# Channel_w_Stim.net
KiCad netlist of a schematic drawn in Altium Designer
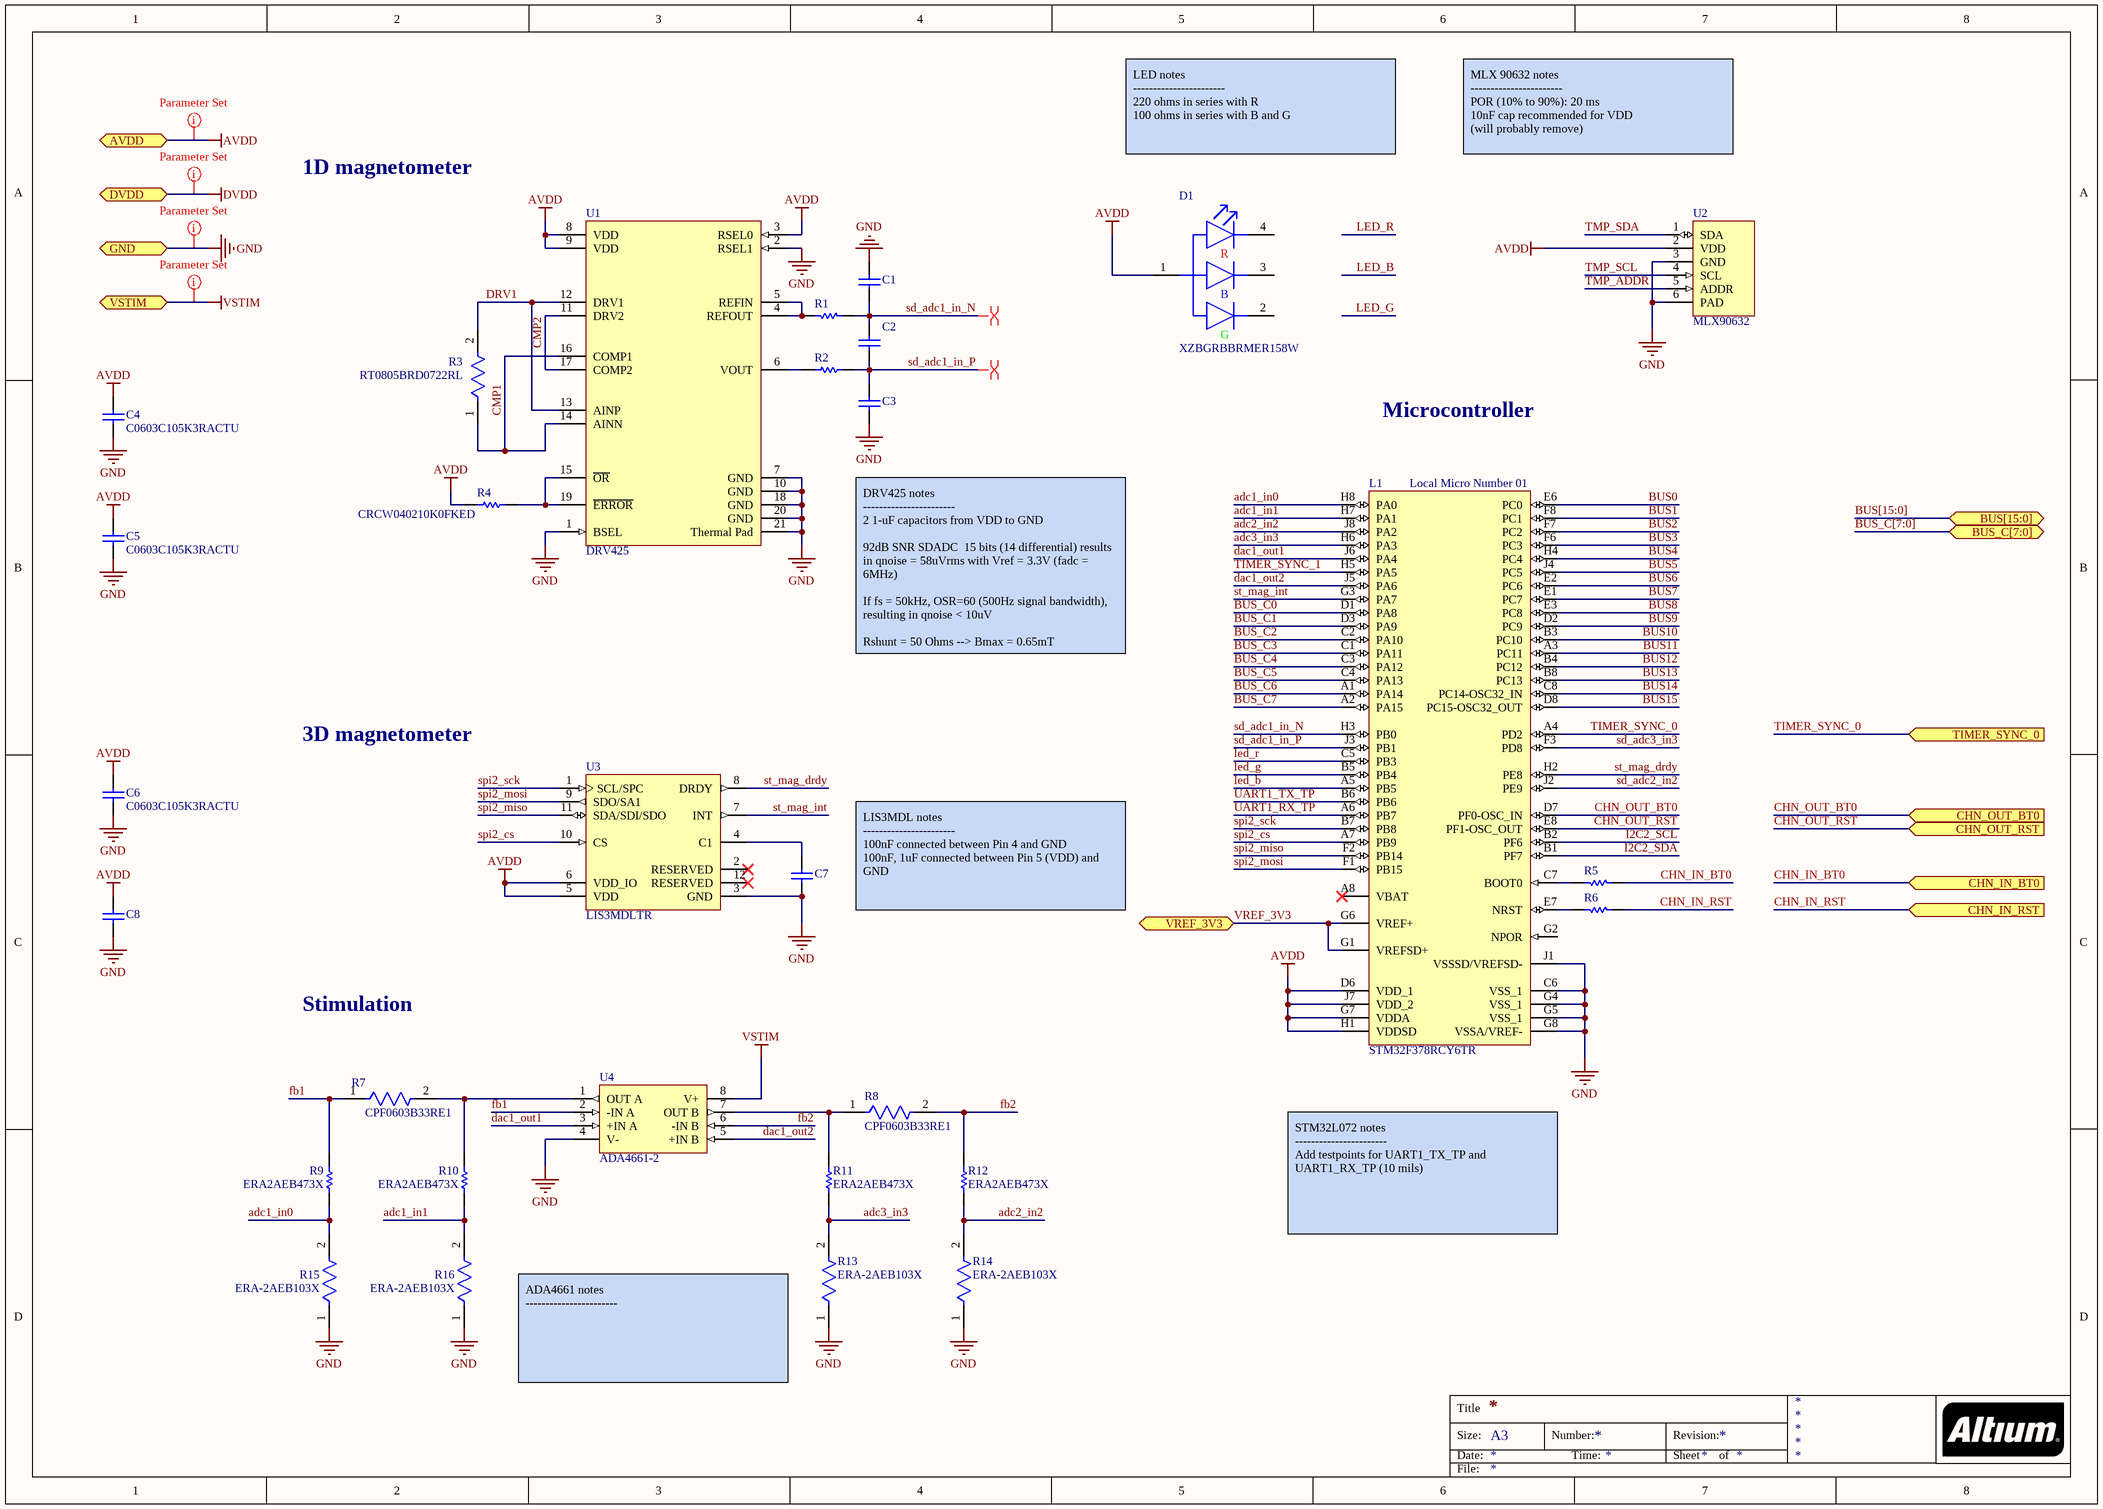
[diagram p0: Channel_w_Stim.SchDoc]

(export (version "E")
  (design (tool "Eeschema 10.0.6"))
  (components
    (comp (ref "C1")
      (value "GRM155R71C103KA01J")
      (footprint "CAPC1005X55X25LL05T10")
      (fields (field (name "MANUFACTURER") "Murata"))
      (libsource (lib "Altium Content Vault") (part "CAP"))
    )
    (comp (ref "C2")
      (value "GRM155R71C104KA88D")
      (footprint "CAPC1005X55X25NL05T10")
      (description "Chip Capacitor, 0.1 uF, +/- 10%, 16 V, -55 to 125 degC, 0402 (1005 Metric), RoHS, Tape and Reel")
      (fields (field (name "VOLTAGE") "16V") (field (name "TOLERANCE") "10%"))
      (libsource (lib "Altium Content Vault") (part "CAP-NP-2"))
    )
    (comp (ref "C3")
      (value "GRM155R71C103KA01J")
      (footprint "CAPC1005X55X25LL05T10")
      (fields (field (name "MANUFACTURER") "Murata"))
      (libsource (lib "Altium Content Vault") (part "CAP"))
    )
    (comp (ref "C4")
      (value "C0603C105K3RACTU")
      (footprint "CAPC1608X87X35LL15T15")
      (fields (field (name "MANUFACTURER") "Kemet"))
      (libsource (lib "Altium Content Vault") (part "CAP"))
    )
    (comp (ref "C5")
      (value "C0603C105K3RACTU")
      (footprint "CAPC1608X87X35LL15T15")
      (fields (field (name "MANUFACTURER") "Kemet"))
      (libsource (lib "Altium Content Vault") (part "CAP"))
    )
    (comp (ref "C6")
      (value "C0603C105K3RACTU")
      (footprint "CAPC1608X87X35LL15T15")
      (fields (field (name "MANUFACTURER") "Kemet"))
      (libsource (lib "Altium Content Vault") (part "CAP"))
    )
    (comp (ref "C7")
      (value "GRM155R71C103KA01J")
      (footprint "CAPC1005X55X25LL05T10")
      (fields (field (name "MANUFACTURER") "Murata"))
      (libsource (lib "Altium Content Vault") (part "CAP"))
    )
    (comp (ref "C8")
      (value "GRM155R71C103KA01J")
      (footprint "CAPC1005X55X25LL05T10")
      (fields (field (name "MANUFACTURER") "Murata"))
      (libsource (lib "Altium Content Vault") (part "CAP"))
    )
    (comp (ref "D1")
      (value "XZBGRBBRMER158W")
      (footprint "4-SMD")
      (description "0.65x0.65x0.20mm (0202) Full-Color Surface Mount LED")
      (libsource (lib "mantarray_library") (part "XZBGRBBRMER158W"))
    )
    (comp (ref "L1")
      (value "STM32F378RCY6TR")
      (footprint "STM-WLCSP66")
      (libsource (lib "Altium Content Vault") (part "MC-ARM-STM32F378-WLCSP66"))
    )
    (comp (ref "R1")
      (value "RC0402FR-071KL")
      (footprint "RESC1005X40X25NL05T10")
      (fields (field (name "MANUFACTURER") "Yageo / Phycomp"))
      (libsource (lib "Altium Content Vault") (part "RES"))
    )
    (comp (ref "R2")
      (value "RC0402FR-071KL")
      (footprint "RESC1005X40X25NL05T10")
      (fields (field (name "MANUFACTURER") "Yageo / Phycomp"))
      (libsource (lib "Altium Content Vault") (part "RES"))
    )
    (comp (ref "R3")
      (value "RT0805BRD0722RL")
      (footprint "FP-RT0805-MFG")
      (description "RES SMD 22 OHM 0.1% 1/8W 0805")
      (fields
        (field (name "OCTOPART") "https://octopart.com/rt0805brd0722rl-yageo-1436111")
        (field (name "TOLERANCE") "0.0025")
      )
      (libsource (lib "Altium Content Vault") (part "1029c3af85768c4190bb7ad29bc67b5"))
    )
    (comp (ref "R4")
      (value "CRCW040210K0FKED")
      (footprint "RESC1005X40X25NL05T05")
      (fields (field (name "MANUFACTURER") "Vishay Dale"))
      (libsource (lib "Altium Content Vault") (part "RES"))
    )
    (comp (ref "R5")
      (value "RC0402FR-071KL")
      (footprint "RESC1005X40X25NL05T10")
      (fields (field (name "MANUFACTURER") "Yageo / Phycomp"))
      (libsource (lib "Altium Content Vault") (part "RES"))
    )
    (comp (ref "R6")
      (value "RC0402FR-071KL")
      (footprint "RESC1005X40X25NL05T10")
      (fields (field (name "MANUFACTURER") "Yageo / Phycomp"))
      (libsource (lib "Altium Content Vault") (part "RES"))
    )
    (comp (ref "R7")
      (value "CPF0603B33RE1")
      (footprint "FP-CPF0603-IPC_C")
      (description "RES SMD 33Ω 0.1% 1/16W 0603")
      (fields
        (field (name "TOLERANCE") "0.1%")
        (field (name "OCTOPART") "https://octopart.com/cpf0603b33re1-te+connectivity-9539400")
      )
      (libsource (lib "Altium Content Vault") (part "1029c3af85768c4190bb7ad29bc67b5"))
    )
    (comp (ref "R8")
      (value "CPF0603B33RE1")
      (footprint "FP-CPF0603-IPC_C")
      (description "RES SMD 33Ω 0.1% 1/16W 0603")
      (fields
        (field (name "TOLERANCE") "0.1%")
        (field (name "OCTOPART") "https://octopart.com/cpf0603b33re1-te+connectivity-9539400")
      )
      (libsource (lib "Altium Content Vault") (part "1029c3af85768c4190bb7ad29bc67b5"))
    )
    (comp (ref "R9")
      (value "ERA2AEB473X")
      (footprint "RESC1005X40X25NL10T10")
      (fields (field (name "MANUFACTURER") "Panasonic"))
      (libsource (lib "Altium Content Vault") (part "RES"))
    )
    (comp (ref "R10")
      (value "ERA2AEB473X")
      (footprint "RESC1005X40X25NL10T10")
      (fields (field (name "MANUFACTURER") "Panasonic"))
      (libsource (lib "Altium Content Vault") (part "RES"))
    )
    (comp (ref "R11")
      (value "ERA2AEB473X")
      (footprint "RESC1005X40X25NL10T10")
      (fields (field (name "MANUFACTURER") "Panasonic"))
      (libsource (lib "Altium Content Vault") (part "RES"))
    )
    (comp (ref "R12")
      (value "ERA2AEB473X")
      (footprint "RESC1005X40X25NL10T10")
      (fields (field (name "MANUFACTURER") "Panasonic"))
      (libsource (lib "Altium Content Vault") (part "RES"))
    )
    (comp (ref "R13")
      (value "ERA-2AEB103X")
      (footprint "FP-ERA2A-MFG")
      (description "RES SMD 10K OHM 0.1% 1/16W 0402")
      (fields (field (name "TOLERANCE") "0.1%") (field (name "MANUFACTURER") "Panasonic"))
      (libsource (lib "Altium Content Vault") (part "1029c3af85768c4190bb7ad29bc67b5"))
    )
    (comp (ref "R14")
      (value "ERA-2AEB103X")
      (footprint "FP-ERA2A-MFG")
      (description "RES SMD 10K OHM 0.1% 1/16W 0402")
      (fields (field (name "TOLERANCE") "0.1%") (field (name "MANUFACTURER") "Panasonic"))
      (libsource (lib "Altium Content Vault") (part "1029c3af85768c4190bb7ad29bc67b5"))
    )
    (comp (ref "R15")
      (value "ERA-2AEB103X")
      (footprint "FP-ERA2A-MFG")
      (description "RES SMD 10K OHM 0.1% 1/16W 0402")
      (fields (field (name "TOLERANCE") "0.1%") (field (name "MANUFACTURER") "Panasonic"))
      (libsource (lib "Altium Content Vault") (part "1029c3af85768c4190bb7ad29bc67b5"))
    )
    (comp (ref "R16")
      (value "ERA-2AEB103X")
      (footprint "FP-ERA2A-MFG")
      (description "RES SMD 10K OHM 0.1% 1/16W 0402")
      (fields (field (name "TOLERANCE") "0.1%") (field (name "MANUFACTURER") "Panasonic"))
      (libsource (lib "Altium Content Vault") (part "1029c3af85768c4190bb7ad29bc67b5"))
    )
    (comp (ref "U1")
      (value "DRV425")
      (footprint "QFN50P400X400X80_HS-21N")
      (description "Texas Instruments Fluxgate Magnetic-Field Sensor")
      (libsource (lib "mantarray_library") (part "DRV425"))
    )
    (comp (ref "U2")
      (value "MLX90632")
      (footprint "SFN 3x3")
      (description "FIR temperature sensor")
      (libsource (lib "mantarray_library") (part "MLX90632"))
    )
    (comp (ref "U3")
      (value "LIS3MDLTR")
      (footprint "STM-LGA-12")
      (fields (field (name "MANUFACTURER") "STMicroelectronics"))
      (libsource (lib "Altium Content Vault") (part "STM-LIS3MDL-LGA-12"))
    )
    (comp (ref "U4")
      (value "ADA4661-2")
      (footprint "LFCSP_WD_8")
      (libsource (lib "mantarray_library") (part "ADA4661-2"))
    )
  )
  (nets
    (net (code "1") (name "/BUS0") (class "Default")
      (node (ref "L1") (pin "E6") (pinfunction "PC0_E6") (pintype "bidirectional"))
    )
    (net (code "2") (name "/BUS1") (class "Default")
      (node (ref "L1") (pin "F8") (pinfunction "PC1_F8") (pintype "bidirectional"))
    )
    (net (code "3") (name "/BUS2") (class "Default")
      (node (ref "L1") (pin "F7") (pinfunction "PC2_F7") (pintype "bidirectional"))
    )
    (net (code "4") (name "/BUS3") (class "Default")
      (node (ref "L1") (pin "F6") (pinfunction "PC3_F6") (pintype "bidirectional"))
    )
    (net (code "5") (name "/BUS4") (class "Default")
      (node (ref "L1") (pin "H4") (pinfunction "PC4_H4") (pintype "bidirectional"))
    )
    (net (code "6") (name "/BUS5") (class "Default")
      (node (ref "L1") (pin "J4") (pinfunction "PC5_J4") (pintype "bidirectional"))
    )
    (net (code "7") (name "/BUS6") (class "Default")
      (node (ref "L1") (pin "E2") (pinfunction "PC6_E2") (pintype "bidirectional"))
    )
    (net (code "8") (name "/BUS7") (class "Default")
      (node (ref "L1") (pin "E1") (pinfunction "PC7_E1") (pintype "bidirectional"))
    )
    (net (code "9") (name "/BUS8") (class "Default")
      (node (ref "L1") (pin "E3") (pinfunction "PC8_E3") (pintype "bidirectional"))
    )
    (net (code "10") (name "/BUS9") (class "Default")
      (node (ref "L1") (pin "D2") (pinfunction "PC9_D2") (pintype "bidirectional"))
    )
    (net (code "11") (name "/BUS10") (class "Default")
      (node (ref "L1") (pin "B3") (pinfunction "PC10_B3") (pintype "bidirectional"))
    )
    (net (code "12") (name "/BUS11") (class "Default")
      (node (ref "L1") (pin "A3") (pinfunction "PC11_A3") (pintype "bidirectional"))
    )
    (net (code "13") (name "/BUS12") (class "Default")
      (node (ref "L1") (pin "B4") (pinfunction "PC12_B4") (pintype "bidirectional"))
    )
    (net (code "14") (name "/BUS13") (class "Default")
      (node (ref "L1") (pin "B8") (pinfunction "PC13_B8") (pintype "bidirectional"))
    )
    (net (code "15") (name "/BUS14") (class "Default")
      (node (ref "L1") (pin "C8") (pinfunction "PC14-OSC32_IN_C8") (pintype "bidirectional"))
    )
    (net (code "16") (name "/BUS15") (class "Default")
      (node (ref "L1") (pin "D8") (pinfunction "PC15-OSC32_OUT_D8") (pintype "bidirectional"))
    )
    (net (code "18") (name "/BUS_C0") (class "Default")
      (node (ref "L1") (pin "D1") (pinfunction "PA8_D1") (pintype "bidirectional"))
    )
    (net (code "19") (name "/BUS_C1") (class "Default")
      (node (ref "L1") (pin "D3") (pinfunction "PA9_D3") (pintype "bidirectional"))
    )
    (net (code "20") (name "/BUS_C2") (class "Default")
      (node (ref "L1") (pin "C2") (pinfunction "PA10_C2") (pintype "bidirectional"))
    )
    (net (code "21") (name "/BUS_C3") (class "Default")
      (node (ref "L1") (pin "C1") (pinfunction "PA11_C1") (pintype "bidirectional"))
    )
    (net (code "22") (name "/BUS_C4") (class "Default")
      (node (ref "L1") (pin "C3") (pinfunction "PA12_C3") (pintype "bidirectional"))
    )
    (net (code "23") (name "/BUS_C5") (class "Default")
      (node (ref "L1") (pin "C4") (pinfunction "PA13_C4") (pintype "bidirectional"))
    )
    (net (code "24") (name "/BUS_C6") (class "Default")
      (node (ref "L1") (pin "A1") (pinfunction "PA14_A1") (pintype "bidirectional"))
    )
    (net (code "25") (name "/BUS_C7") (class "Default")
      (node (ref "L1") (pin "A2") (pinfunction "PA15_A2") (pintype "bidirectional"))
    )
    (net (code "27") (name "/CHN_IN_BT0") (class "Default")
      (node (ref "R5") (pin "2") (pinfunction "2_2") (pintype "passive"))
    )
    (net (code "28") (name "/CHN_IN_RST") (class "Default")
      (node (ref "R6") (pin "2") (pinfunction "2_2") (pintype "passive"))
    )
    (net (code "29") (name "/CHN_OUT_BT0") (class "Default")
      (node (ref "L1") (pin "D7") (pinfunction "PF0-OSC_IN_D7") (pintype "bidirectional"))
    )
    (net (code "30") (name "/CHN_OUT_RST") (class "Default")
      (node (ref "L1") (pin "E8") (pinfunction "PF1-OSC_OUT_E8") (pintype "bidirectional"))
    )
    (net (code "31") (name "/CMP1") (class "Default")
      (node (ref "R3") (pin "1") (pinfunction "1_1") (pintype "passive"))
      (node (ref "U1") (pin "14") (pinfunction "AINN_14") (pintype "passive"))
      (node (ref "U1") (pin "16") (pinfunction "COMP1_16") (pintype "passive"))
    )
    (net (code "32") (name "/CMP2") (class "Default")
      (node (ref "U1") (pin "11") (pinfunction "DRV2_11") (pintype "passive"))
      (node (ref "U1") (pin "17") (pinfunction "COMP2_17") (pintype "passive"))
    )
    (net (code "33") (name "/DRV1") (class "Default")
      (node (ref "R3") (pin "2") (pinfunction "2_2") (pintype "passive"))
      (node (ref "U1") (pin "12") (pinfunction "DRV1_12") (pintype "passive"))
      (node (ref "U1") (pin "13") (pinfunction "AINP_13") (pintype "passive"))
    )
    (net (code "34") (name "/I2C2_SCL") (class "Default")
      (node (ref "L1") (pin "B2") (pinfunction "PF6_B2") (pintype "bidirectional"))
    )
    (net (code "35") (name "/I2C2_SDA") (class "Default")
      (node (ref "L1") (pin "B1") (pinfunction "PF7_B1") (pintype "bidirectional"))
    )
    (net (code "39") (name "/TIMER_SYNC_0") (class "Default")
      (node (ref "L1") (pin "A4") (pinfunction "PD2_A4") (pintype "bidirectional"))
    )
    (net (code "40") (name "/TIMER_SYNC_1") (class "Default")
      (node (ref "L1") (pin "H5") (pinfunction "PA5_H5") (pintype "bidirectional"))
    )
    (net (code "41") (name "/TMP_ADDR") (class "Default")
      (node (ref "U2") (pin "5") (pinfunction "ADDR_5") (pintype "input"))
    )
    (net (code "42") (name "/TMP_SCL") (class "Default")
      (node (ref "U2") (pin "4") (pinfunction "SCL_4") (pintype "input"))
    )
    (net (code "43") (name "/TMP_SDA") (class "Default")
      (node (ref "U2") (pin "1") (pinfunction "SDA_1") (pintype "bidirectional"))
    )
    (net (code "44") (name "/UART1_RX_TP") (class "Default")
      (node (ref "L1") (pin "A6") (pinfunction "PB7_A6") (pintype "bidirectional"))
    )
    (net (code "45") (name "/UART1_TX_TP") (class "Default")
      (node (ref "L1") (pin "B6") (pinfunction "PB6_B6") (pintype "bidirectional"))
    )
    (net (code "46") (name "/VREF_3V3") (class "Default")
      (node (ref "L1") (pin "G1") (pinfunction "VREFSD+_G1") (pintype "power_in"))
      (node (ref "L1") (pin "G6") (pinfunction "VREF+_G6") (pintype "power_in"))
    )
    (net (code "47") (name "/adc1_in0") (class "Default")
      (node (ref "L1") (pin "H8") (pinfunction "PA0_H8") (pintype "bidirectional"))
      (node (ref "R15") (pin "2") (pinfunction "2_2") (pintype "passive"))
      (node (ref "R9") (pin "1") (pinfunction "1_1") (pintype "passive"))
    )
    (net (code "48") (name "/adc1_in1") (class "Default")
      (node (ref "L1") (pin "H7") (pinfunction "PA1_H7") (pintype "bidirectional"))
      (node (ref "R10") (pin "1") (pinfunction "1_1") (pintype "passive"))
      (node (ref "R16") (pin "2") (pinfunction "2_2") (pintype "passive"))
    )
    (net (code "49") (name "/adc2_in2") (class "Default")
      (node (ref "L1") (pin "J8") (pinfunction "PA2_J8") (pintype "bidirectional"))
      (node (ref "R12") (pin "1") (pinfunction "1_1") (pintype "passive"))
      (node (ref "R14") (pin "2") (pinfunction "2_2") (pintype "passive"))
    )
    (net (code "50") (name "/adc3_in3") (class "Default")
      (node (ref "L1") (pin "H6") (pinfunction "PA3_H6") (pintype "bidirectional"))
      (node (ref "R11") (pin "1") (pinfunction "1_1") (pintype "passive"))
      (node (ref "R13") (pin "2") (pinfunction "2_2") (pintype "passive"))
    )
    (net (code "51") (name "/dac1_out1") (class "Default")
      (node (ref "L1") (pin "J6") (pinfunction "PA4_J6") (pintype "bidirectional"))
      (node (ref "U4") (pin "3") (pinfunction "+IN_A_3") (pintype "input"))
    )
    (net (code "52") (name "/dac1_out2") (class "Default")
      (node (ref "L1") (pin "J5") (pinfunction "PA6_J5") (pintype "bidirectional"))
      (node (ref "U4") (pin "5") (pinfunction "+IN_B_5") (pintype "input"))
    )
    (net (code "53") (name "/fb1") (class "Default")
      (node (ref "R7") (pin "1") (pinfunction "1_1") (pintype "passive"))
      (node (ref "R9") (pin "2") (pinfunction "2_2") (pintype "passive"))
      (node (ref "U4") (pin "2") (pinfunction "-IN_A_2") (pintype "input"))
    )
    (net (code "54") (name "/fb2") (class "Default")
      (node (ref "R12") (pin "2") (pinfunction "2_2") (pintype "passive"))
      (node (ref "R8") (pin "2") (pinfunction "2_2") (pintype "passive"))
      (node (ref "U4") (pin "6") (pinfunction "-IN_B_6") (pintype "input"))
    )
    (net (code "55") (name "/led_b") (class "Default")
      (node (ref "L1") (pin "A5") (pinfunction "PB5_A5") (pintype "bidirectional"))
    )
    (net (code "56") (name "/led_g") (class "Default")
      (node (ref "L1") (pin "B5") (pinfunction "PB4_B5") (pintype "bidirectional"))
    )
    (net (code "57") (name "/led_r") (class "Default")
      (node (ref "L1") (pin "C5") (pinfunction "PB3_C5") (pintype "bidirectional"))
    )
    (net (code "58") (name "/sd_adc1_in_N") (class "Default")
      (node (ref "C1") (pin "2") (pinfunction "2_2") (pintype "passive"))
      (node (ref "C2") (pin "2") (pinfunction "2_2") (pintype "passive"))
      (node (ref "L1") (pin "H3") (pinfunction "PB0_H3") (pintype "bidirectional"))
      (node (ref "R1") (pin "2") (pinfunction "2_2") (pintype "passive"))
    )
    (net (code "59") (name "/sd_adc1_in_P") (class "Default")
      (node (ref "C2") (pin "1") (pinfunction "1_1") (pintype "passive"))
      (node (ref "C3") (pin "2") (pinfunction "2_2") (pintype "passive"))
      (node (ref "L1") (pin "J3") (pinfunction "PB1_J3") (pintype "bidirectional"))
      (node (ref "R2") (pin "2") (pinfunction "2_2") (pintype "passive"))
    )
    (net (code "60") (name "/sd_adc2_in2") (class "Default")
      (node (ref "L1") (pin "J2") (pinfunction "PE9_J2") (pintype "bidirectional"))
    )
    (net (code "61") (name "/sd_adc3_in3") (class "Default")
      (node (ref "L1") (pin "F3") (pinfunction "PD8_F3") (pintype "bidirectional"))
    )
    (net (code "62") (name "/spi2_cs") (class "Default")
      (node (ref "L1") (pin "A7") (pinfunction "PB9_A7") (pintype "bidirectional"))
      (node (ref "U3") (pin "10") (pinfunction "CS_10") (pintype "input"))
    )
    (net (code "63") (name "/spi2_miso") (class "Default")
      (node (ref "L1") (pin "F2") (pinfunction "PB14_F2") (pintype "bidirectional"))
      (node (ref "U3") (pin "11") (pinfunction "SDA/SDI/SDO_11") (pintype "bidirectional"))
    )
    (net (code "64") (name "/spi2_mosi") (class "Default")
      (node (ref "L1") (pin "F1") (pinfunction "PB15_F1") (pintype "bidirectional"))
      (node (ref "U3") (pin "9") (pinfunction "SDO/SA1_9") (pintype "output"))
    )
    (net (code "65") (name "/spi2_sck") (class "Default")
      (node (ref "L1") (pin "B7") (pinfunction "PB8_B7") (pintype "bidirectional"))
      (node (ref "U3") (pin "1") (pinfunction "SCL/SPC_1") (pintype "input"))
    )
    (net (code "66") (name "/st_mag_drdy") (class "Default")
      (node (ref "L1") (pin "H2") (pinfunction "PE8_H2") (pintype "bidirectional"))
      (node (ref "U3") (pin "8") (pinfunction "DRDY_8") (pintype "output"))
    )
    (net (code "67") (name "/st_mag_int") (class "Default")
      (node (ref "L1") (pin "G3") (pinfunction "PA7_G3") (pintype "bidirectional"))
      (node (ref "U3") (pin "7") (pinfunction "INT_7") (pintype "output"))
    )
    (net (code "68") (name "AVDD") (class "Default")
      (node (ref "C4") (pin "2") (pinfunction "2_2") (pintype "passive"))
      (node (ref "C5") (pin "2") (pinfunction "2_2") (pintype "passive"))
      (node (ref "C6") (pin "2") (pinfunction "2_2") (pintype "passive"))
      (node (ref "C8") (pin "2") (pinfunction "2_2") (pintype "passive"))
      (node (ref "D1") (pin "1") (pinfunction "1_1") (pintype "passive"))
      (node (ref "L1") (pin "D6") (pinfunction "VDD_1_D6") (pintype "power_in"))
      (node (ref "L1") (pin "G7") (pinfunction "VDDA_G7") (pintype "power_in"))
      (node (ref "L1") (pin "H1") (pinfunction "VDDSD_H1") (pintype "power_in"))
      (node (ref "L1") (pin "J7") (pinfunction "VDD_2_J7") (pintype "power_in"))
      (node (ref "R4") (pin "1") (pinfunction "1_1") (pintype "passive"))
      (node (ref "U1") (pin "3") (pinfunction "RSEL0_3") (pintype "input"))
      (node (ref "U1") (pin "8") (pinfunction "VDD_8") (pintype "power_in"))
      (node (ref "U1") (pin "9") (pinfunction "VDD_9") (pintype "power_in"))
      (node (ref "U2") (pin "2") (pinfunction "VDD_2") (pintype "power_in"))
      (node (ref "U3") (pin "5") (pinfunction "VDD_5") (pintype "power_in"))
      (node (ref "U3") (pin "6") (pinfunction "VDD_IO_6") (pintype "power_in"))
    )
    (net (code "70") (name "GND") (class "Default")
      (node (ref "C1") (pin "1") (pinfunction "1_1") (pintype "passive"))
      (node (ref "C3") (pin "1") (pinfunction "1_1") (pintype "passive"))
      (node (ref "C4") (pin "1") (pinfunction "1_1") (pintype "passive"))
      (node (ref "C5") (pin "1") (pinfunction "1_1") (pintype "passive"))
      (node (ref "C6") (pin "1") (pinfunction "1_1") (pintype "passive"))
      (node (ref "C7") (pin "1") (pinfunction "1_1") (pintype "passive"))
      (node (ref "C8") (pin "1") (pinfunction "1_1") (pintype "passive"))
      (node (ref "L1") (pin "C6") (pinfunction "VSS_1_C6") (pintype "power_in"))
      (node (ref "L1") (pin "G4") (pinfunction "VSS_1_G4") (pintype "power_in"))
      (node (ref "L1") (pin "G5") (pinfunction "VSS_1_G5") (pintype "power_in"))
      (node (ref "L1") (pin "G8") (pinfunction "VSSA/VREF-_G8") (pintype "power_in"))
      (node (ref "L1") (pin "J1") (pinfunction "VSSSD/VREFSD-_J1") (pintype "power_in"))
      (node (ref "R13") (pin "1") (pinfunction "1_1") (pintype "passive"))
      (node (ref "R14") (pin "1") (pinfunction "1_1") (pintype "passive"))
      (node (ref "R15") (pin "1") (pinfunction "1_1") (pintype "passive"))
      (node (ref "R16") (pin "1") (pinfunction "1_1") (pintype "passive"))
      (node (ref "U1") (pin "1") (pinfunction "BSEL_1") (pintype "input"))
      (node (ref "U1") (pin "10") (pinfunction "GND_10") (pintype "power_in"))
      (node (ref "U1") (pin "18") (pinfunction "GND_18") (pintype "power_in"))
      (node (ref "U1") (pin "2") (pinfunction "RSEL1_2") (pintype "input"))
      (node (ref "U1") (pin "20") (pinfunction "GND_20") (pintype "power_in"))
      (node (ref "U1") (pin "21") (pinfunction "Thermal_Pad_21") (pintype "passive"))
      (node (ref "U1") (pin "7") (pinfunction "GND_7") (pintype "power_in"))
      (node (ref "U2") (pin "3") (pinfunction "GND_3") (pintype "power_in"))
      (node (ref "U2") (pin "6") (pinfunction "PAD_6") (pintype "passive"))
      (node (ref "U3") (pin "3") (pinfunction "GND_3") (pintype "power_in"))
      (node (ref "U4") (pin "4") (pinfunction "V-_4") (pintype "power_in"))
    )
    (net (code "71") (name "Net-(L1-BOOT0)") (class "Default")
      (node (ref "L1") (pin "C7") (pinfunction "BOOT0_C7") (pintype "input"))
      (node (ref "R5") (pin "1") (pinfunction "1_1") (pintype "passive"))
    )
    (net (code "72") (name "Net-(L1-NRST)") (class "Default")
      (node (ref "L1") (pin "E7") (pinfunction "NRST_E7") (pintype "bidirectional"))
      (node (ref "R6") (pin "1") (pinfunction "1_1") (pintype "passive"))
    )
    (net (code "73") (name "Net-(U1-REFIN)") (class "Default")
      (node (ref "R1") (pin "1") (pinfunction "1_1") (pintype "passive"))
      (node (ref "U1") (pin "4") (pinfunction "REFOUT_4") (pintype "passive"))
      (node (ref "U1") (pin "5") (pinfunction "REFIN_5") (pintype "passive"))
    )
    (net (code "74") (name "Net-(U1-VOUT)") (class "Default")
      (node (ref "R2") (pin "1") (pinfunction "1_1") (pintype "passive"))
      (node (ref "U1") (pin "6") (pinfunction "VOUT_6") (pintype "passive"))
    )
    (net (code "75") (name "Net-(U1-~{ERROR})") (class "Default")
      (node (ref "R4") (pin "2") (pinfunction "2_2") (pintype "passive"))
      (node (ref "U1") (pin "15") (pinfunction "~{OR}_15") (pintype "passive"))
      (node (ref "U1") (pin "19") (pinfunction "~{ERROR}_19") (pintype "passive"))
    )
    (net (code "76") (name "Net-(U3-C1)") (class "Default")
      (node (ref "C7") (pin "2") (pinfunction "2_2") (pintype "passive"))
      (node (ref "U3") (pin "4") (pinfunction "C1_4") (pintype "passive"))
    )
    (net (code "77") (name "Net-(U4-OUT_A)") (class "Default")
      (node (ref "R10") (pin "2") (pinfunction "2_2") (pintype "passive"))
      (node (ref "R7") (pin "2") (pinfunction "2_2") (pintype "passive"))
      (node (ref "U4") (pin "1") (pinfunction "OUT_A_1") (pintype "output"))
    )
    (net (code "78") (name "Net-(U4-OUT_B)") (class "Default")
      (node (ref "R11") (pin "2") (pinfunction "2_2") (pintype "passive"))
      (node (ref "R8") (pin "1") (pinfunction "1_1") (pintype "passive"))
      (node (ref "U4") (pin "7") (pinfunction "OUT_B_7") (pintype "output"))
    )
    (net (code "79") (name "VSTIM") (class "Default")
      (node (ref "U4") (pin "8") (pinfunction "V+_8") (pintype "power_in"))
    )
    (net (code "80") (name "unconnected-(D1-Pad2)") (class "Default")
      (node (ref "D1") (pin "2") (pinfunction "2_2") (pintype "passive"))
    )
    (net (code "81") (name "unconnected-(D1-Pad3)") (class "Default")
      (node (ref "D1") (pin "3") (pinfunction "3_3") (pintype "passive"))
    )
    (net (code "82") (name "unconnected-(D1-Pad4)") (class "Default")
      (node (ref "D1") (pin "4") (pinfunction "4_4") (pintype "passive"))
    )
    (net (code "83") (name "unconnected-(L1-NPOR-PadG2)") (class "Default")
      (node (ref "L1") (pin "G2") (pinfunction "NPOR_G2") (pintype "input"))
    )
    (net (code "84") (name "unconnected-(L1-VBAT-PadA8)") (class "Default")
      (node (ref "L1") (pin "A8") (pinfunction "VBAT_A8") (pintype "power_in+no_connect"))
    )
    (net (code "85") (name "unconnected-(U3-RESERVED-Pad2)") (class "Default")
      (node (ref "U3") (pin "2") (pinfunction "RESERVED_2") (pintype "passive+no_connect"))
    )
    (net (code "86") (name "unconnected-(U3-RESERVED-Pad12)") (class "Default")
      (node (ref "U3") (pin "12") (pinfunction "RESERVED_12") (pintype "passive+no_connect"))
    )
  )
)
